# FridgeWarninig_0_2.net
KiCad netlist of a schematic drawn in EAGLE
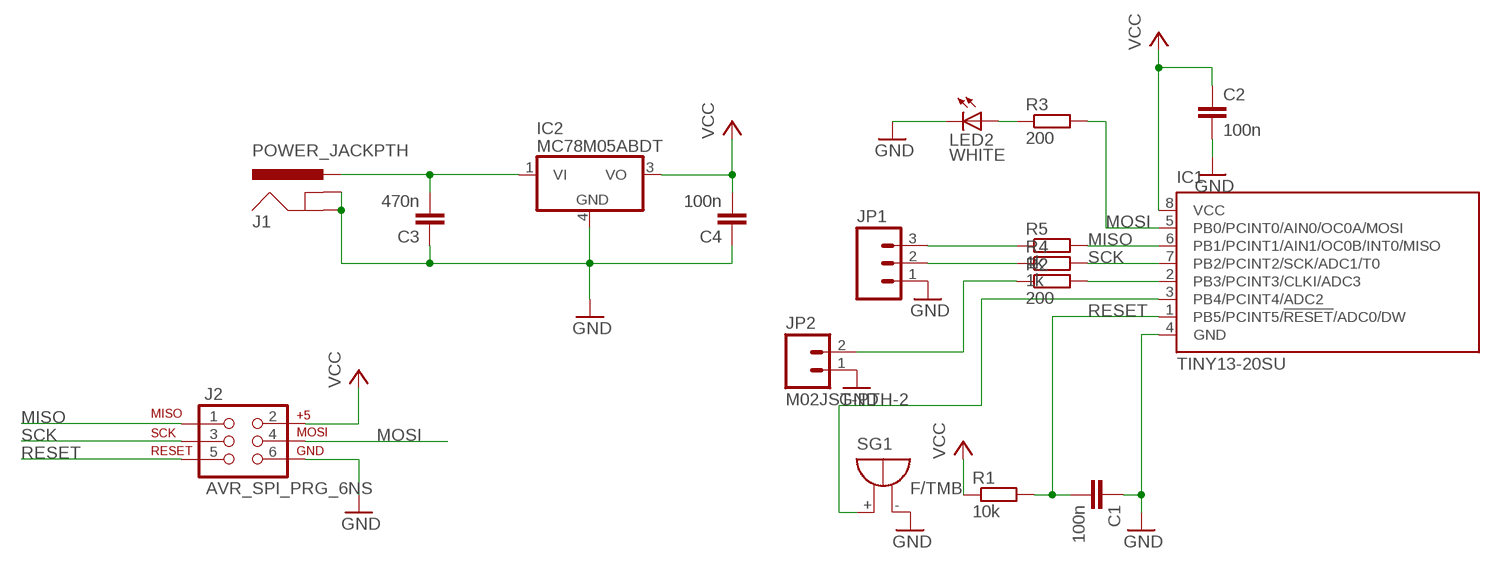
[diagram p0: schematic, sheet 1]

(export (version "E")
  (design (tool "Eeschema 10.0.6"))
  (components
    (comp (ref "C1")
      (value "100n")
      (footprint "eagle-import:C0805")
      (libsource (lib "eagle-import") (part "C-EUC0805"))
    )
    (comp (ref "C2")
      (value "100n")
      (footprint "eagle-import:C0805")
      (libsource (lib "eagle-import") (part "C-EUC0805"))
    )
    (comp (ref "C3")
      (value "470n")
      (footprint "eagle-import:C0805")
      (libsource (lib "eagle-import") (part "C-EUC0805"))
    )
    (comp (ref "C4")
      (value "100n")
      (footprint "eagle-import:C0805")
      (libsource (lib "eagle-import") (part "C-EUC0805"))
    )
    (comp (ref "IC1")
      (value "TINY13-20SU")
      (footprint "eagle-import:8S2")
      (fields (field (name "MPN") "ATTINY13-20SU"))
      (libsource (lib "eagle-import") (part "TINY13SU-20"))
    )
    (comp (ref "IC2")
      (value "MC78M05ABDT")
      (footprint "eagle-import:DPACK_3")
      (libsource (lib "eagle-import") (part "MC78M05ABDT"))
    )
    (comp (ref "J1")
      (value "POWER_JACKPTH")
      (footprint "eagle-import:POWER_JACK_PTH")
      (libsource (lib "eagle-import") (part "POWER_JACKPTH"))
    )
    (comp (ref "J2")
      (value "AVR_SPI_PRG_6NS")
      (footprint "eagle-import:2X3-NS")
      (libsource (lib "eagle-import") (part "AVR_SPI_PRG_6NS"))
    )
    (comp (ref "JP1")
      (value "M03JST-PTH")
      (footprint "eagle-import:JST-3-PTH")
      (libsource (lib "eagle-import") (part "M03JST-PTH"))
    )
    (comp (ref "JP2")
      (value "M02JST-PTH-2")
      (footprint "eagle-import:JST-2-PTH")
      (libsource (lib "eagle-import") (part "M02JST-PTH-2"))
    )
    (comp (ref "LED2")
      (value "WHITE")
      (footprint "eagle-import:CHIP-LED0603")
      (libsource (lib "eagle-import") (part "LEDCHIP-LED0603"))
    )
    (comp (ref "R1")
      (value "10k")
      (footprint "eagle-import:R0805")
      (libsource (lib "eagle-import") (part "R-EU_R0805"))
    )
    (comp (ref "R2")
      (value "200")
      (footprint "eagle-import:R0805")
      (libsource (lib "eagle-import") (part "R-EU_R0805"))
    )
    (comp (ref "R3")
      (value "200")
      (footprint "eagle-import:R0603")
      (libsource (lib "eagle-import") (part "R-EU_R0603"))
    )
    (comp (ref "R4")
      (value "1k")
      (footprint "eagle-import:R0805")
      (libsource (lib "eagle-import") (part "R-EU_R0805"))
    )
    (comp (ref "R5")
      (value "1k")
      (footprint "eagle-import:R0805")
      (libsource (lib "eagle-import") (part "R-EU_R0805"))
    )
    (comp (ref "SG1")
      (value "F/TMB")
      (footprint "eagle-import:F_TMB")
      (libsource (lib "eagle-import") (part "F/TMB"))
    )
  )
  (nets
    (net (code "1") (name "/MISO") (class "Default")
      (node (ref "IC1") (pin "6") (pinfunction "PB1/PCINT1/AIN1/OC0B/INT0/MISO_6") (pintype "bidirectional"))
      (node (ref "J2") (pin "1") (pinfunction "1_1") (pintype "passive"))
      (node (ref "R5") (pin "2") (pinfunction "2_2") (pintype "passive"))
    )
    (net (code "2") (name "/MOSI") (class "Default")
      (node (ref "IC1") (pin "5") (pinfunction "PB0/PCINT0/AIN0/OC0A/MOSI_5") (pintype "bidirectional"))
      (node (ref "J2") (pin "4") (pinfunction "4_4") (pintype "passive"))
      (node (ref "R3") (pin "2") (pinfunction "2_2") (pintype "passive"))
    )
    (net (code "3") (name "/RESET") (class "Default")
      (node (ref "C1") (pin "2") (pinfunction "2_2") (pintype "passive"))
      (node (ref "IC1") (pin "1") (pinfunction "PB5/PCINT5/~{RESET}/ADC0/DW_1") (pintype "bidirectional"))
      (node (ref "J2") (pin "5") (pinfunction "5_5") (pintype "passive"))
      (node (ref "R1") (pin "2") (pinfunction "2_2") (pintype "passive"))
    )
    (net (code "4") (name "/SCK") (class "Default")
      (node (ref "IC1") (pin "7") (pinfunction "PB2/PCINT2/SCK/ADC1/T0_7") (pintype "bidirectional"))
      (node (ref "J2") (pin "3") (pinfunction "3_3") (pintype "passive"))
      (node (ref "R4") (pin "2") (pinfunction "2_2") (pintype "passive"))
    )
    (net (code "5") (name "GND") (class "Default")
      (node (ref "C1") (pin "1") (pinfunction "1_1") (pintype "passive"))
      (node (ref "C2") (pin "2") (pinfunction "2_2") (pintype "passive"))
      (node (ref "C3") (pin "1") (pinfunction "1_1") (pintype "passive"))
      (node (ref "C4") (pin "1") (pinfunction "1_1") (pintype "passive"))
      (node (ref "IC1") (pin "4") (pinfunction "GND_4") (pintype "power_in"))
      (node (ref "IC2") (pin "4") (pinfunction "GND_4") (pintype "passive"))
      (node (ref "J1") (pin "GND") (pinfunction "GND_GND") (pintype "bidirectional"))
      (node (ref "J1") (pin "GNDBREAK") (pinfunction "GNDBREAK_GNDBREAK") (pintype "bidirectional"))
      (node (ref "J2") (pin "6") (pinfunction "6_6") (pintype "passive"))
      (node (ref "JP1") (pin "1") (pinfunction "1_1") (pintype "passive"))
      (node (ref "JP2") (pin "1") (pinfunction "1_1") (pintype "passive"))
      (node (ref "LED2") (pin "C") (pinfunction "C_C") (pintype "passive"))
      (node (ref "SG1") (pin "-") (pinfunction "-_-") (pintype "passive"))
    )
    (net (code "6") (name "Net-(IC1-PB3{slash}PCINT3{slash}CLKI{slash}ADC3)") (class "Default")
      (node (ref "IC1") (pin "2") (pinfunction "PB3/PCINT3/CLKI/ADC3_2") (pintype "bidirectional"))
      (node (ref "R2") (pin "2") (pinfunction "2_2") (pintype "passive"))
    )
    (net (code "7") (name "Net-(IC1-PB4{slash}PCINT4{slash}ADC2)") (class "Default")
      (node (ref "IC1") (pin "3") (pinfunction "PB4/PCINT4/ADC2_3") (pintype "bidirectional"))
      (node (ref "SG1") (pin "+") (pinfunction "+_+") (pintype "passive"))
    )
    (net (code "8") (name "Net-(IC2-VI)") (class "Default")
      (node (ref "C3") (pin "2") (pinfunction "2_2") (pintype "passive"))
      (node (ref "IC2") (pin "1") (pinfunction "VI_1") (pintype "input"))
      (node (ref "J1") (pin "PWR") (pinfunction "PWR_PWR") (pintype "bidirectional"))
    )
    (net (code "9") (name "Net-(JP1-Pad2)") (class "Default")
      (node (ref "JP1") (pin "2") (pinfunction "2_2") (pintype "passive"))
      (node (ref "R4") (pin "1") (pinfunction "1_1") (pintype "passive"))
    )
    (net (code "10") (name "Net-(JP1-Pad3)") (class "Default")
      (node (ref "JP1") (pin "3") (pinfunction "3_3") (pintype "passive"))
      (node (ref "R5") (pin "1") (pinfunction "1_1") (pintype "passive"))
    )
    (net (code "11") (name "Net-(JP2-Pad2)") (class "Default")
      (node (ref "JP2") (pin "2") (pinfunction "2_2") (pintype "passive"))
      (node (ref "R2") (pin "1") (pinfunction "1_1") (pintype "passive"))
    )
    (net (code "12") (name "Net-(LED2-PadA)") (class "Default")
      (node (ref "LED2") (pin "A") (pinfunction "A_A") (pintype "passive"))
      (node (ref "R3") (pin "1") (pinfunction "1_1") (pintype "passive"))
    )
    (net (code "13") (name "VCC") (class "Default")
      (node (ref "C2") (pin "1") (pinfunction "1_1") (pintype "passive"))
      (node (ref "C4") (pin "2") (pinfunction "2_2") (pintype "passive"))
      (node (ref "IC1") (pin "8") (pinfunction "VCC_8") (pintype "power_in"))
      (node (ref "IC2") (pin "3") (pinfunction "VO_3") (pintype "passive"))
      (node (ref "J2") (pin "2") (pinfunction "2_2") (pintype "passive"))
      (node (ref "R1") (pin "1") (pinfunction "1_1") (pintype "passive"))
    )
  )
)
